# Sheet1.net
KiCad netlist of a schematic drawn in Altium Designer
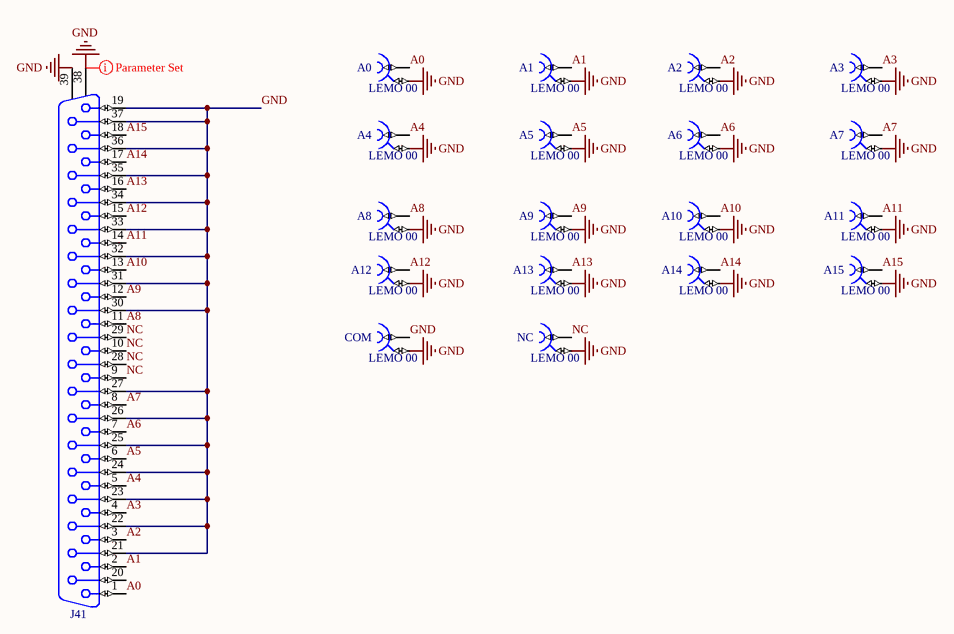
[diagram p0: Sheet1.SchDoc]

(export (version "E")
  (design (tool "Eeschema 10.0.6"))
  (components
    (comp (ref "A0")
      (value "LEMO 00")
      (footprint "LEMO_EPA.00.250.NTN")
      (fields
        (field (name "PART NUMBER") "LEMO_EPA.00.250.NTN")
        (field (name "MANUFACTURER") "LEMO")
        (field (name "MANUFACTURER PART NUMBER") "EPA.00.250.NTN")
        (field (name "AUTHOR") "CERN DEM JLC")
      )
      (libsource (lib "Connectors") (part "Coax_1Female_1Shield"))
    )
    (comp (ref "A1")
      (value "LEMO 00")
      (footprint "LEMO_EPA.00.250.NTN")
      (fields
        (field (name "PART NUMBER") "LEMO_EPA.00.250.NTN")
        (field (name "MANUFACTURER") "LEMO")
        (field (name "MANUFACTURER PART NUMBER") "EPA.00.250.NTN")
        (field (name "AUTHOR") "CERN DEM JLC")
      )
      (libsource (lib "Connectors") (part "Coax_1Female_1Shield"))
    )
    (comp (ref "A2")
      (value "LEMO 00")
      (footprint "LEMO_EPA.00.250.NTN")
      (fields
        (field (name "PART NUMBER") "LEMO_EPA.00.250.NTN")
        (field (name "MANUFACTURER") "LEMO")
        (field (name "MANUFACTURER PART NUMBER") "EPA.00.250.NTN")
        (field (name "AUTHOR") "CERN DEM JLC")
      )
      (libsource (lib "Connectors") (part "Coax_1Female_1Shield"))
    )
    (comp (ref "A3")
      (value "LEMO 00")
      (footprint "LEMO_EPA.00.250.NTN")
      (fields
        (field (name "PART NUMBER") "LEMO_EPA.00.250.NTN")
        (field (name "MANUFACTURER") "LEMO")
        (field (name "MANUFACTURER PART NUMBER") "EPA.00.250.NTN")
        (field (name "AUTHOR") "CERN DEM JLC")
      )
      (libsource (lib "Connectors") (part "Coax_1Female_1Shield"))
    )
    (comp (ref "A4")
      (value "LEMO 00")
      (footprint "LEMO_EPA.00.250.NTN")
      (fields
        (field (name "PART NUMBER") "LEMO_EPA.00.250.NTN")
        (field (name "MANUFACTURER") "LEMO")
        (field (name "MANUFACTURER PART NUMBER") "EPA.00.250.NTN")
        (field (name "AUTHOR") "CERN DEM JLC")
      )
      (libsource (lib "Connectors") (part "Coax_1Female_1Shield"))
    )
    (comp (ref "A5")
      (value "LEMO 00")
      (footprint "LEMO_EPA.00.250.NTN")
      (fields
        (field (name "PART NUMBER") "LEMO_EPA.00.250.NTN")
        (field (name "MANUFACTURER") "LEMO")
        (field (name "MANUFACTURER PART NUMBER") "EPA.00.250.NTN")
        (field (name "AUTHOR") "CERN DEM JLC")
      )
      (libsource (lib "Connectors") (part "Coax_1Female_1Shield"))
    )
    (comp (ref "A6")
      (value "LEMO 00")
      (footprint "LEMO_EPA.00.250.NTN")
      (fields
        (field (name "PART NUMBER") "LEMO_EPA.00.250.NTN")
        (field (name "MANUFACTURER") "LEMO")
        (field (name "MANUFACTURER PART NUMBER") "EPA.00.250.NTN")
        (field (name "AUTHOR") "CERN DEM JLC")
      )
      (libsource (lib "Connectors") (part "Coax_1Female_1Shield"))
    )
    (comp (ref "A7")
      (value "LEMO 00")
      (footprint "LEMO_EPA.00.250.NTN")
      (fields
        (field (name "PART NUMBER") "LEMO_EPA.00.250.NTN")
        (field (name "MANUFACTURER") "LEMO")
        (field (name "MANUFACTURER PART NUMBER") "EPA.00.250.NTN")
        (field (name "AUTHOR") "CERN DEM JLC")
      )
      (libsource (lib "Connectors") (part "Coax_1Female_1Shield"))
    )
    (comp (ref "A8")
      (value "LEMO 00")
      (footprint "LEMO_EPA.00.250.NTN")
      (fields
        (field (name "PART NUMBER") "LEMO_EPA.00.250.NTN")
        (field (name "MANUFACTURER") "LEMO")
        (field (name "MANUFACTURER PART NUMBER") "EPA.00.250.NTN")
        (field (name "AUTHOR") "CERN DEM JLC")
      )
      (libsource (lib "Connectors") (part "Coax_1Female_1Shield"))
    )
    (comp (ref "A9")
      (value "LEMO 00")
      (footprint "LEMO_EPA.00.250.NTN")
      (fields
        (field (name "PART NUMBER") "LEMO_EPA.00.250.NTN")
        (field (name "MANUFACTURER") "LEMO")
        (field (name "MANUFACTURER PART NUMBER") "EPA.00.250.NTN")
        (field (name "AUTHOR") "CERN DEM JLC")
      )
      (libsource (lib "Connectors") (part "Coax_1Female_1Shield"))
    )
    (comp (ref "A10")
      (value "LEMO 00")
      (footprint "LEMO_EPA.00.250.NTN")
      (fields
        (field (name "PART NUMBER") "LEMO_EPA.00.250.NTN")
        (field (name "MANUFACTURER") "LEMO")
        (field (name "MANUFACTURER PART NUMBER") "EPA.00.250.NTN")
        (field (name "AUTHOR") "CERN DEM JLC")
      )
      (libsource (lib "Connectors") (part "Coax_1Female_1Shield"))
    )
    (comp (ref "A11")
      (value "LEMO 00")
      (footprint "LEMO_EPA.00.250.NTN")
      (fields
        (field (name "PART NUMBER") "LEMO_EPA.00.250.NTN")
        (field (name "MANUFACTURER") "LEMO")
        (field (name "MANUFACTURER PART NUMBER") "EPA.00.250.NTN")
        (field (name "AUTHOR") "CERN DEM JLC")
      )
      (libsource (lib "Connectors") (part "Coax_1Female_1Shield"))
    )
    (comp (ref "A12")
      (value "LEMO 00")
      (footprint "LEMO_EPA.00.250.NTN")
      (fields
        (field (name "PART NUMBER") "LEMO_EPA.00.250.NTN")
        (field (name "MANUFACTURER") "LEMO")
        (field (name "MANUFACTURER PART NUMBER") "EPA.00.250.NTN")
        (field (name "AUTHOR") "CERN DEM JLC")
      )
      (libsource (lib "Connectors") (part "Coax_1Female_1Shield"))
    )
    (comp (ref "A13")
      (value "LEMO 00")
      (footprint "LEMO_EPA.00.250.NTN")
      (fields
        (field (name "PART NUMBER") "LEMO_EPA.00.250.NTN")
        (field (name "MANUFACTURER") "LEMO")
        (field (name "MANUFACTURER PART NUMBER") "EPA.00.250.NTN")
        (field (name "AUTHOR") "CERN DEM JLC")
      )
      (libsource (lib "Connectors") (part "Coax_1Female_1Shield"))
    )
    (comp (ref "A14")
      (value "LEMO 00")
      (footprint "LEMO_EPA.00.250.NTN")
      (fields
        (field (name "PART NUMBER") "LEMO_EPA.00.250.NTN")
        (field (name "MANUFACTURER") "LEMO")
        (field (name "MANUFACTURER PART NUMBER") "EPA.00.250.NTN")
        (field (name "AUTHOR") "CERN DEM JLC")
      )
      (libsource (lib "Connectors") (part "Coax_1Female_1Shield"))
    )
    (comp (ref "A15")
      (value "LEMO 00")
      (footprint "LEMO_EPA.00.250.NTN")
      (fields
        (field (name "PART NUMBER") "LEMO_EPA.00.250.NTN")
        (field (name "MANUFACTURER") "LEMO")
        (field (name "MANUFACTURER PART NUMBER") "EPA.00.250.NTN")
        (field (name "AUTHOR") "CERN DEM JLC")
      )
      (libsource (lib "Connectors") (part "Coax_1Female_1Shield"))
    )
    (comp (ref "COM")
      (value "LEMO 00")
      (footprint "LEMO_EPA.00.250.NTN")
      (fields
        (field (name "PART NUMBER") "LEMO_EPA.00.250.NTN")
        (field (name "MANUFACTURER") "LEMO")
        (field (name "MANUFACTURER PART NUMBER") "EPA.00.250.NTN")
        (field (name "AUTHOR") "CERN DEM JLC")
      )
      (libsource (lib "Connectors") (part "Coax_1Female_1Shield"))
    )
    (comp (ref "J41")
      (value "D-SUB37F")
      (footprint "NORCOMP_172-037-242R011")
      (description "Connector D-sub 37 Female")
      (fields
        (field (name "PART NUMBER") "NORCOMP_172-037-242R011")
        (field (name "MANUFACTURER") "NORCOMP")
        (field (name "AUTHOR") "CERN DEM MR")
      )
      (libsource (lib "Connectors") (part "Connector D-sub 37 Female"))
    )
    (comp (ref "NC")
      (value "LEMO 00")
      (footprint "LEMO_EPA.00.250.NTN")
      (fields
        (field (name "PART NUMBER") "LEMO_EPA.00.250.NTN")
        (field (name "MANUFACTURER") "LEMO")
        (field (name "MANUFACTURER PART NUMBER") "EPA.00.250.NTN")
        (field (name "AUTHOR") "CERN DEM JLC")
      )
      (libsource (lib "Connectors") (part "Coax_1Female_1Shield"))
    )
  )
  (nets
    (net (code "1") (name "/A0") (class "Default")
      (node (ref "A0") (pin "1") (pinfunction "1_1") (pintype "bidirectional"))
      (node (ref "J41") (pin "1") (pinfunction "1_1") (pintype "bidirectional"))
    )
    (net (code "2") (name "/A1") (class "Default")
      (node (ref "A1") (pin "1") (pinfunction "1_1") (pintype "bidirectional"))
      (node (ref "J41") (pin "2") (pinfunction "2_2") (pintype "bidirectional"))
    )
    (net (code "3") (name "/A2") (class "Default")
      (node (ref "A2") (pin "1") (pinfunction "1_1") (pintype "bidirectional"))
      (node (ref "J41") (pin "3") (pinfunction "3_3") (pintype "bidirectional"))
    )
    (net (code "4") (name "/A3") (class "Default")
      (node (ref "A3") (pin "1") (pinfunction "1_1") (pintype "bidirectional"))
      (node (ref "J41") (pin "4") (pinfunction "4_4") (pintype "bidirectional"))
    )
    (net (code "5") (name "/A4") (class "Default")
      (node (ref "A4") (pin "1") (pinfunction "1_1") (pintype "bidirectional"))
      (node (ref "J41") (pin "5") (pinfunction "5_5") (pintype "bidirectional"))
    )
    (net (code "6") (name "/A5") (class "Default")
      (node (ref "A5") (pin "1") (pinfunction "1_1") (pintype "bidirectional"))
      (node (ref "J41") (pin "6") (pinfunction "6_6") (pintype "bidirectional"))
    )
    (net (code "7") (name "/A6") (class "Default")
      (node (ref "A6") (pin "1") (pinfunction "1_1") (pintype "bidirectional"))
      (node (ref "J41") (pin "7") (pinfunction "7_7") (pintype "bidirectional"))
    )
    (net (code "8") (name "/A7") (class "Default")
      (node (ref "A7") (pin "1") (pinfunction "1_1") (pintype "bidirectional"))
      (node (ref "J41") (pin "8") (pinfunction "8_8") (pintype "bidirectional"))
    )
    (net (code "9") (name "/A8") (class "Default")
      (node (ref "A8") (pin "1") (pinfunction "1_1") (pintype "bidirectional"))
      (node (ref "J41") (pin "11") (pinfunction "11_11") (pintype "bidirectional"))
    )
    (net (code "10") (name "/A9") (class "Default")
      (node (ref "A9") (pin "1") (pinfunction "1_1") (pintype "bidirectional"))
      (node (ref "J41") (pin "12") (pinfunction "12_12") (pintype "bidirectional"))
    )
    (net (code "11") (name "/A10") (class "Default")
      (node (ref "A10") (pin "1") (pinfunction "1_1") (pintype "bidirectional"))
      (node (ref "J41") (pin "13") (pinfunction "13_13") (pintype "bidirectional"))
    )
    (net (code "12") (name "/A11") (class "Default")
      (node (ref "A11") (pin "1") (pinfunction "1_1") (pintype "bidirectional"))
      (node (ref "J41") (pin "14") (pinfunction "14_14") (pintype "bidirectional"))
    )
    (net (code "13") (name "/A12") (class "Default")
      (node (ref "A12") (pin "1") (pinfunction "1_1") (pintype "bidirectional"))
      (node (ref "J41") (pin "15") (pinfunction "15_15") (pintype "bidirectional"))
    )
    (net (code "14") (name "/A13") (class "Default")
      (node (ref "A13") (pin "1") (pinfunction "1_1") (pintype "bidirectional"))
      (node (ref "J41") (pin "16") (pinfunction "16_16") (pintype "bidirectional"))
    )
    (net (code "15") (name "/A14") (class "Default")
      (node (ref "A14") (pin "1") (pinfunction "1_1") (pintype "bidirectional"))
      (node (ref "J41") (pin "17") (pinfunction "17_17") (pintype "bidirectional"))
    )
    (net (code "16") (name "/A15") (class "Default")
      (node (ref "A15") (pin "1") (pinfunction "1_1") (pintype "bidirectional"))
      (node (ref "J41") (pin "18") (pinfunction "18_18") (pintype "bidirectional"))
    )
    (net (code "17") (name "/NC") (class "Default")
      (node (ref "J41") (pin "10") (pinfunction "10_10") (pintype "bidirectional"))
      (node (ref "J41") (pin "28") (pinfunction "28_28") (pintype "bidirectional"))
      (node (ref "J41") (pin "29") (pinfunction "29_29") (pintype "bidirectional"))
      (node (ref "J41") (pin "9") (pinfunction "9_9") (pintype "bidirectional"))
      (node (ref "NC") (pin "1") (pinfunction "1_1") (pintype "bidirectional"))
    )
    (net (code "18") (name "GND") (class "Default")
      (node (ref "A0") (pin "2") (pinfunction "2_2") (pintype "bidirectional"))
      (node (ref "A1") (pin "2") (pinfunction "2_2") (pintype "bidirectional"))
      (node (ref "A10") (pin "2") (pinfunction "2_2") (pintype "bidirectional"))
      (node (ref "A11") (pin "2") (pinfunction "2_2") (pintype "bidirectional"))
      (node (ref "A12") (pin "2") (pinfunction "2_2") (pintype "bidirectional"))
      (node (ref "A13") (pin "2") (pinfunction "2_2") (pintype "bidirectional"))
      (node (ref "A14") (pin "2") (pinfunction "2_2") (pintype "bidirectional"))
      (node (ref "A15") (pin "2") (pinfunction "2_2") (pintype "bidirectional"))
      (node (ref "A2") (pin "2") (pinfunction "2_2") (pintype "bidirectional"))
      (node (ref "A3") (pin "2") (pinfunction "2_2") (pintype "bidirectional"))
      (node (ref "A4") (pin "2") (pinfunction "2_2") (pintype "bidirectional"))
      (node (ref "A5") (pin "2") (pinfunction "2_2") (pintype "bidirectional"))
      (node (ref "A6") (pin "2") (pinfunction "2_2") (pintype "bidirectional"))
      (node (ref "A7") (pin "2") (pinfunction "2_2") (pintype "bidirectional"))
      (node (ref "A8") (pin "2") (pinfunction "2_2") (pintype "bidirectional"))
      (node (ref "A9") (pin "2") (pinfunction "2_2") (pintype "bidirectional"))
      (node (ref "COM") (pin "1") (pinfunction "1_1") (pintype "bidirectional"))
      (node (ref "COM") (pin "2") (pinfunction "2_2") (pintype "bidirectional"))
      (node (ref "J41") (pin "19") (pinfunction "19_19") (pintype "bidirectional"))
      (node (ref "J41") (pin "21") (pinfunction "21_21") (pintype "bidirectional"))
      (node (ref "J41") (pin "22") (pinfunction "22_22") (pintype "bidirectional"))
      (node (ref "J41") (pin "23") (pinfunction "23_23") (pintype "bidirectional"))
      (node (ref "J41") (pin "24") (pinfunction "24_24") (pintype "bidirectional"))
      (node (ref "J41") (pin "25") (pinfunction "25_25") (pintype "bidirectional"))
      (node (ref "J41") (pin "26") (pinfunction "26_26") (pintype "bidirectional"))
      (node (ref "J41") (pin "27") (pinfunction "27_27") (pintype "bidirectional"))
      (node (ref "J41") (pin "30") (pinfunction "30_30") (pintype "bidirectional"))
      (node (ref "J41") (pin "31") (pinfunction "31_31") (pintype "bidirectional"))
      (node (ref "J41") (pin "32") (pinfunction "32_32") (pintype "bidirectional"))
      (node (ref "J41") (pin "33") (pinfunction "33_33") (pintype "bidirectional"))
      (node (ref "J41") (pin "34") (pinfunction "34_34") (pintype "bidirectional"))
      (node (ref "J41") (pin "35") (pinfunction "35_35") (pintype "bidirectional"))
      (node (ref "J41") (pin "36") (pinfunction "36_36") (pintype "bidirectional"))
      (node (ref "J41") (pin "37") (pinfunction "37_37") (pintype "bidirectional"))
      (node (ref "J41") (pin "38") (pinfunction "38_38") (pintype "passive"))
      (node (ref "J41") (pin "39") (pinfunction "39_39") (pintype "passive"))
      (node (ref "NC") (pin "2") (pinfunction "2_2") (pintype "bidirectional"))
    )
    (net (code "19") (name "unconnected-(J41-Pad20)") (class "Default")
      (node (ref "J41") (pin "20") (pinfunction "20_20") (pintype "bidirectional"))
    )
  )
)
